# RS422.net
KiCad netlist of a schematic drawn in Altium Designer
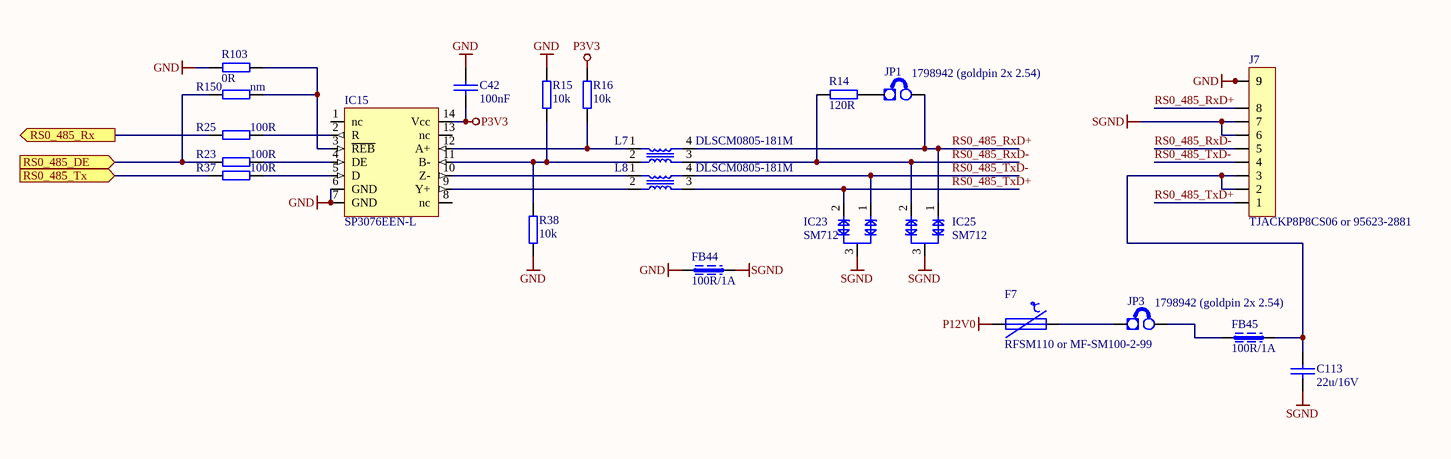
[diagram p0: RS422.SchDoc]

(export (version "E")
  (design (tool "Eeschema 10.0.6"))
  (components
    (comp (ref "C42")
      (value "100nF")
      (footprint "0402C")
      (description "Capacitor SMD")
      (libsource (lib "LIBRARY_SCH") (part "CAP_SMD_0402"))
    )
    (comp (ref "C113")
      (value "22u/16V")
      (footprint "1206C")
      (description "Capacitor SMD")
      (libsource (lib "LIBRARY_SCH") (part "CAP_SMD_0805"))
    )
    (comp (ref "F7")
      (value "RFSM110 or MF-SM100-2-99")
      (footprint "SMD150-2")
      (description "2.50A/15V")
      (libsource (lib "LIBRARY_SCH") (part "F_PTC_9.5x6mm"))
    )
    (comp (ref "FB44")
      (value "100R/1A")
      (footprint "0603L")
      (description "ferrite bead 100R@100MHz 1A")
      (libsource (lib "LIBRARY_SCH") (part "L_FERRITE_BEAD_0603"))
    )
    (comp (ref "FB45")
      (value "100R/1A")
      (footprint "0603L")
      (description "ferrite bead 100R@100MHz 1A")
      (libsource (lib "LIBRARY_SCH") (part "L_FERRITE_BEAD_0603"))
    )
    (comp (ref "IC15")
      (value "SP3076EEN-L")
      (footprint "SO-14")
      (description "3.3V, 1/8 Load, Failsafe  RS-485/RS422 Transceivers")
      (libsource (lib "LIBRARY_SCH") (part "DRV_SP3070/73/76"))
    )
    (comp (ref "IC23")
      (value "SM712")
      (footprint "SOT-23")
      (description "Asymmetrical TVS Diode for RS485")
      (libsource (lib "LIBRARY_SCH") (part "D_TVS_SM712"))
    )
    (comp (ref "IC25")
      (value "SM712")
      (footprint "SOT-23")
      (description "Asymmetrical TVS Diode for RS485")
      (libsource (lib "LIBRARY_SCH") (part "D_TVS_SM712"))
    )
    (comp (ref "J7")
      (value "TJACKP8P8CS06 or 95623-2881")
      (footprint "ETH_VERT_95623-2881")
      (description "Modular 8pin (Maritex or Molex)")
      (libsource (lib "LIBRARY_SCH") (part "CON_MOD_8pin_V"))
    )
    (comp (ref "JP1")
      (value "1798942 (goldpin 2x 2.54)")
      (footprint "jump")
      (description "Jumper")
      (libsource (lib "LIBRARY_SCH") (part "JUMPER"))
    )
    (comp (ref "JP3")
      (value "1798942 (goldpin 2x 2.54)")
      (footprint "jump")
      (description "Jumper")
      (libsource (lib "LIBRARY_SCH") (part "JUMPER"))
    )
    (comp (ref "L7")
      (value "DLSCM0805-181M")
      (footprint "DLSCM0805")
      (description "CMC 180R")
      (libsource (lib "LIBRARY_SCH") (part "L_CMC_DLSCM0805_180R"))
    )
    (comp (ref "L8")
      (value "DLSCM0805-181M")
      (footprint "DLSCM0805")
      (description "CMC 180R")
      (libsource (lib "LIBRARY_SCH") (part "L_CMC_DLSCM0805_180R"))
    )
    (comp (ref "R14")
      (value "120R")
      (footprint "1206R")
      (description "SMD Resistor")
      (libsource (lib "LIBRARY_SCH") (part "RES_1206"))
    )
    (comp (ref "R15")
      (value "10k")
      (footprint "0402R")
      (description "SMD Resistor")
      (libsource (lib "LIBRARY_SCH") (part "RES_0402"))
    )
    (comp (ref "R16")
      (value "10k")
      (footprint "0402R")
      (description "SMD Resistor")
      (libsource (lib "LIBRARY_SCH") (part "RES_0402"))
    )
    (comp (ref "R23")
      (value "100R")
      (footprint "0402R")
      (description "SMD Resistor")
      (libsource (lib "LIBRARY_SCH") (part "RES_0402"))
    )
    (comp (ref "R25")
      (value "100R")
      (footprint "0402R")
      (description "SMD Resistor")
      (libsource (lib "LIBRARY_SCH") (part "RES_0402"))
    )
    (comp (ref "R37")
      (value "100R")
      (footprint "0402R")
      (description "SMD Resistor")
      (libsource (lib "LIBRARY_SCH") (part "RES_0402"))
    )
    (comp (ref "R38")
      (value "10k")
      (footprint "0402R")
      (description "SMD Resistor")
      (libsource (lib "LIBRARY_SCH") (part "RES_0402"))
    )
    (comp (ref "R103")
      (value "0R")
      (footprint "0603R")
      (description "SMD Resistor")
      (libsource (lib "LIBRARY_SCH") (part "RES_0603"))
    )
    (comp (ref "R150")
      (value "nm")
      (footprint "0402R")
      (description "SMD Resistor")
      (libsource (lib "LIBRARY_SCH") (part "RES_0402"))
    )
  )
  (nets
    (net (code "1") (name "/RS0_485_DE") (class "Default")
      (node (ref "R150") (pin "1") (pinfunction "1_1") (pintype "passive"))
      (node (ref "R23") (pin "1") (pinfunction "1_1") (pintype "passive"))
    )
    (net (code "2") (name "/RS0_485_Rx") (class "Default")
      (node (ref "R25") (pin "1") (pinfunction "1_1") (pintype "passive"))
    )
    (net (code "3") (name "/RS0_485_RxD+") (class "Default")
      (node (ref "IC25") (pin "1") (pinfunction "1_1") (pintype "passive"))
      (node (ref "J7") (pin "8") (pinfunction "8_8") (pintype "passive"))
      (node (ref "JP1") (pin "2") (pinfunction "E2_2") (pintype "passive"))
      (node (ref "L7") (pin "4") (pinfunction "4_4") (pintype "passive"))
    )
    (net (code "4") (name "/RS0_485_RxD-") (class "Default")
      (node (ref "IC25") (pin "2") (pinfunction "2_2") (pintype "passive"))
      (node (ref "J7") (pin "5") (pinfunction "5_5") (pintype "passive"))
      (node (ref "L7") (pin "3") (pinfunction "3_3") (pintype "passive"))
      (node (ref "R14") (pin "1") (pinfunction "1_1") (pintype "passive"))
    )
    (net (code "5") (name "/RS0_485_Tx") (class "Default")
      (node (ref "R37") (pin "1") (pinfunction "1_1") (pintype "passive"))
    )
    (net (code "6") (name "/RS0_485_TxD+") (class "Default")
      (node (ref "IC23") (pin "2") (pinfunction "2_2") (pintype "passive"))
      (node (ref "J7") (pin "1") (pinfunction "1_1") (pintype "passive"))
      (node (ref "L8") (pin "3") (pinfunction "3_3") (pintype "passive"))
    )
    (net (code "7") (name "/RS0_485_TxD-") (class "Default")
      (node (ref "IC23") (pin "1") (pinfunction "1_1") (pintype "passive"))
      (node (ref "J7") (pin "4") (pinfunction "4_4") (pintype "passive"))
      (node (ref "L8") (pin "4") (pinfunction "4_4") (pintype "passive"))
    )
    (net (code "8") (name "GND") (class "Default")
      (node (ref "C42") (pin "1") (pinfunction "1_1") (pintype "passive"))
      (node (ref "FB44") (pin "1") (pinfunction "1_1") (pintype "passive"))
      (node (ref "IC15") (pin "6") (pinfunction "GND_6") (pintype "power_in"))
      (node (ref "IC15") (pin "7") (pinfunction "GND_7") (pintype "power_in"))
      (node (ref "J7") (pin "9a") (pinfunction "9_9a") (pintype "passive"))
      (node (ref "J7") (pin "9b") (pinfunction "9_9b") (pintype "passive"))
      (node (ref "R103") (pin "1") (pinfunction "1_1") (pintype "passive"))
      (node (ref "R15") (pin "2") (pinfunction "2_2") (pintype "passive"))
      (node (ref "R38") (pin "1") (pinfunction "1_1") (pintype "passive"))
    )
    (net (code "9") (name "Net-(C113-Pad1)") (class "Default")
      (node (ref "C113") (pin "1") (pinfunction "1_1") (pintype "passive"))
      (node (ref "FB45") (pin "2") (pinfunction "2_2") (pintype "passive"))
      (node (ref "J7") (pin "2") (pinfunction "2_2") (pintype "passive"))
      (node (ref "J7") (pin "3") (pinfunction "3_3") (pintype "passive"))
    )
    (net (code "10") (name "Net-(IC15-A+)") (class "Default")
      (node (ref "IC15") (pin "12") (pinfunction "A+_12") (pintype "input"))
      (node (ref "L7") (pin "1") (pinfunction "1_1") (pintype "passive"))
      (node (ref "R16") (pin "1") (pinfunction "1_1") (pintype "passive"))
    )
    (net (code "11") (name "Net-(IC15-B-)") (class "Default")
      (node (ref "IC15") (pin "11") (pinfunction "B-_11") (pintype "input"))
      (node (ref "L7") (pin "2") (pinfunction "2_2") (pintype "passive"))
      (node (ref "R15") (pin "1") (pinfunction "1_1") (pintype "passive"))
      (node (ref "R38") (pin "2") (pinfunction "2_2") (pintype "passive"))
    )
    (net (code "12") (name "Net-(IC15-D)") (class "Default")
      (node (ref "IC15") (pin "5") (pinfunction "D_5") (pintype "input"))
      (node (ref "R37") (pin "2") (pinfunction "2_2") (pintype "passive"))
    )
    (net (code "13") (name "Net-(IC15-DE)") (class "Default")
      (node (ref "IC15") (pin "4") (pinfunction "DE_4") (pintype "input"))
      (node (ref "R23") (pin "2") (pinfunction "2_2") (pintype "passive"))
    )
    (net (code "14") (name "Net-(IC15-R)") (class "Default")
      (node (ref "IC15") (pin "2") (pinfunction "R_2") (pintype "output"))
      (node (ref "R25") (pin "2") (pinfunction "2_2") (pintype "passive"))
    )
    (net (code "15") (name "Net-(IC15-Y+)") (class "Default")
      (node (ref "IC15") (pin "9") (pinfunction "Y+_9") (pintype "output"))
      (node (ref "L8") (pin "2") (pinfunction "2_2") (pintype "passive"))
    )
    (net (code "16") (name "Net-(IC15-Z-)") (class "Default")
      (node (ref "IC15") (pin "10") (pinfunction "Z-_10") (pintype "output"))
      (node (ref "L8") (pin "1") (pinfunction "1_1") (pintype "passive"))
    )
    (net (code "17") (name "Net-(IC15-~{REB})") (class "Default")
      (node (ref "IC15") (pin "3") (pinfunction "~{REB}_3") (pintype "input"))
      (node (ref "R103") (pin "2") (pinfunction "2_2") (pintype "passive"))
      (node (ref "R150") (pin "2") (pinfunction "2_2") (pintype "passive"))
    )
    (net (code "18") (name "Net-(JP1-E1)") (class "Default")
      (node (ref "JP1") (pin "1") (pinfunction "E1_1") (pintype "passive"))
      (node (ref "R14") (pin "2") (pinfunction "2_2") (pintype "passive"))
    )
    (net (code "19") (name "Net-(JP3-E1)") (class "Default")
      (node (ref "F7") (pin "2") (pinfunction "2_2") (pintype "passive"))
      (node (ref "JP3") (pin "1") (pinfunction "E1_1") (pintype "passive"))
    )
    (net (code "20") (name "Net-(JP3-E2)") (class "Default")
      (node (ref "FB45") (pin "1") (pinfunction "1_1") (pintype "passive"))
      (node (ref "JP3") (pin "2") (pinfunction "E2_2") (pintype "passive"))
    )
    (net (code "21") (name "P3V3") (class "Default")
      (node (ref "C42") (pin "2") (pinfunction "2_2") (pintype "passive"))
      (node (ref "IC15") (pin "14") (pinfunction "Vcc_14") (pintype "power_in"))
      (node (ref "R16") (pin "2") (pinfunction "2_2") (pintype "passive"))
    )
    (net (code "22") (name "P12V0") (class "Default")
      (node (ref "F7") (pin "1") (pinfunction "1_1") (pintype "passive"))
    )
    (net (code "23") (name "SGND") (class "Default")
      (node (ref "C113") (pin "2") (pinfunction "2_2") (pintype "passive"))
      (node (ref "FB44") (pin "2") (pinfunction "2_2") (pintype "passive"))
      (node (ref "IC23") (pin "3") (pinfunction "3_3") (pintype "passive"))
      (node (ref "IC25") (pin "3") (pinfunction "3_3") (pintype "passive"))
      (node (ref "J7") (pin "6") (pinfunction "6_6") (pintype "passive"))
      (node (ref "J7") (pin "7") (pinfunction "7_7") (pintype "passive"))
    )
    (net (code "24") (name "unconnected-(IC15-nc-Pad1)") (class "Default")
      (node (ref "IC15") (pin "1") (pinfunction "nc_1") (pintype "passive"))
    )
    (net (code "25") (name "unconnected-(IC15-nc-Pad8)") (class "Default")
      (node (ref "IC15") (pin "8") (pinfunction "nc_8") (pintype "passive"))
    )
    (net (code "26") (name "unconnected-(IC15-nc-Pad13)") (class "Default")
      (node (ref "IC15") (pin "13") (pinfunction "nc_13") (pintype "passive"))
    )
  )
)
